# Spannungswandlung.net
KiCad netlist of a schematic drawn in Altium Designer
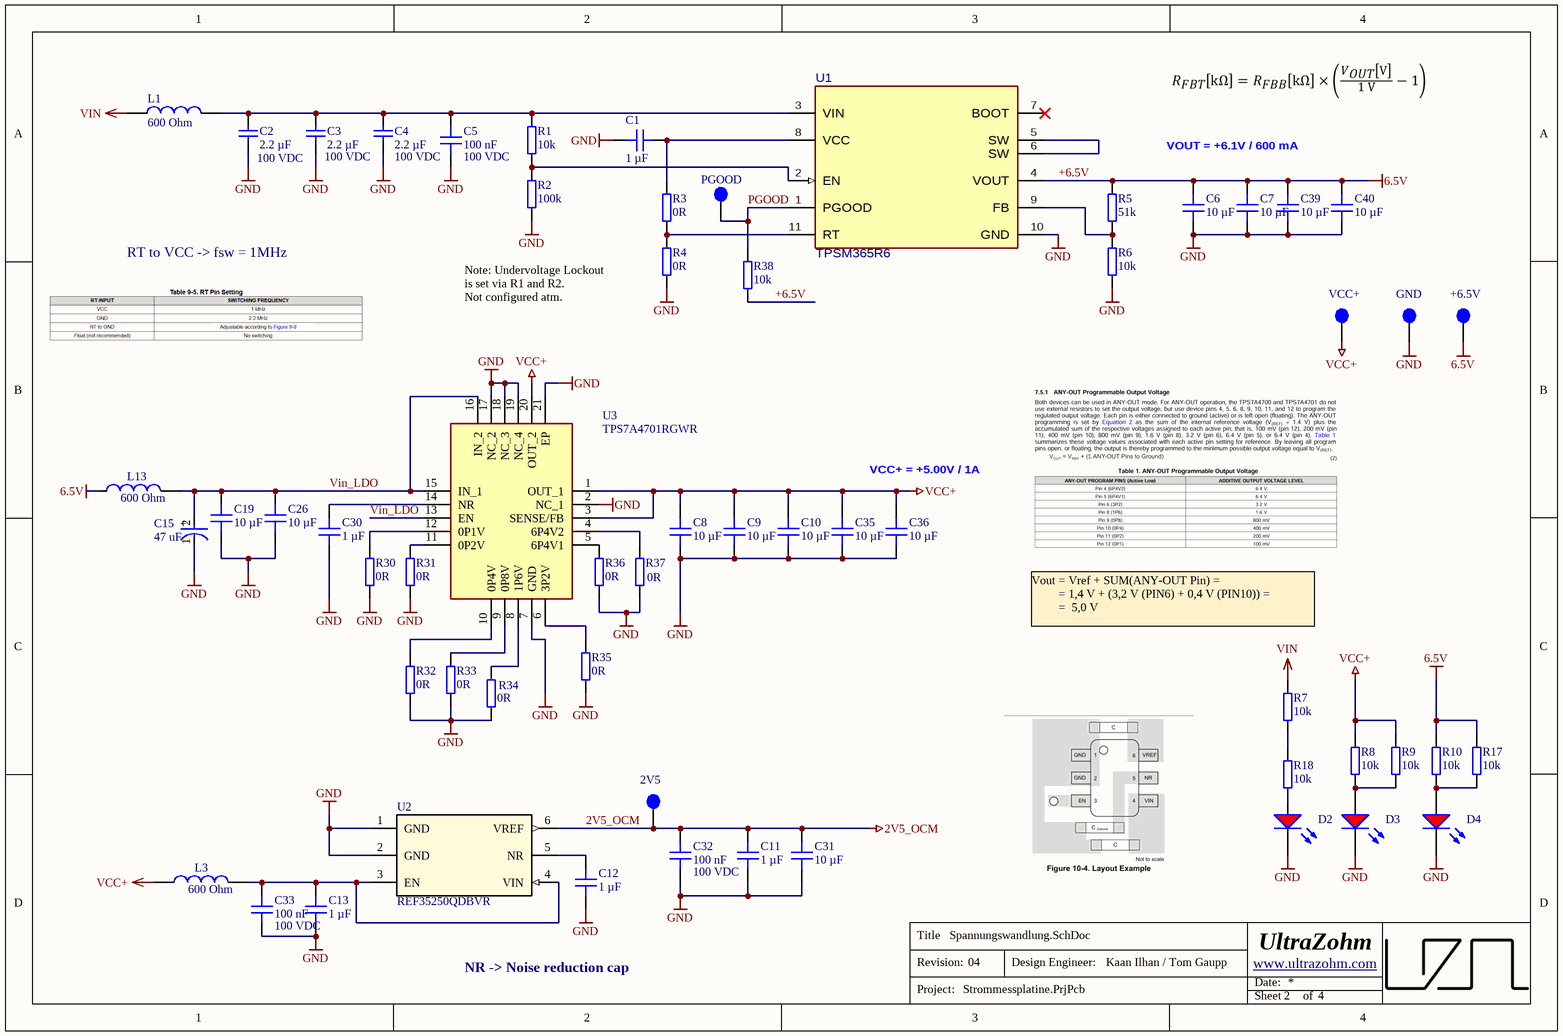
[diagram p0: Spannungswandlung.SchDoc]

(export (version "E")
  (design (tool "Eeschema 10.0.6"))
  (components
    (comp (ref "+6.5V")
      (value "6.5 V")
      (footprint "TP_1mm")
      (description "Testpoint 1mm")
      (fields
        (field (name "MANUFACTURER PART NUMBER") "NULL")
        (field (name "CREATED") "2018_06_25_AGeiger")
        (field (name "CREATED FROM") "AGeiger")
      )
      (libsource (lib "user") (part "TP_1mm"))
    )
    (comp (ref "2V5")
      (value "2V5")
      (footprint "TP_1mm")
      (description "Testpoint 1mm")
      (fields
        (field (name "MANUFACTURER PART NUMBER") "NULL")
        (field (name "CREATED") "2018_06_25_AGeiger")
        (field (name "CREATED FROM") "AGeiger")
      )
      (libsource (lib "user") (part "TP_1mm"))
    )
    (comp (ref "C1")
      (value "1 µF")
      (footprint "C_0603")
      (description "50V 1uF X5R ±10% 0603  Multilayer Ceramic Capacitors MLCC - SMD/SMT ROHS")
      (fields
        (field (name "MANUFACTURER PART NUMBER") "CL10A105KB8NNNC")
        (field (name "MANUFACTURER") "Samsung Electro-Mechanics")
        (field (name "CREATED FROM") "MGremer")
      )
      (libsource (lib "user") (part "Capacitor"))
    )
    (comp (ref "C2")
      (value "2.2 µF")
      (footprint "C_1210_TE")
      (description "100V 2.2uF X7R ±10% 1210 Multilayer Ceramic Capacitors MLCC - SMD/SMT ROHS")
      (fields
        (field (name "MANUFACTURER PART NUMBER") "FS32X225K101EGG")
        (field (name "MANUFACTURER") "PSA(Prosperity Dielectrics)")
        (field (name "VOLTAGE RATING") "100 VDC")
        (field (name "CREATED FROM") "AGeiger")
      )
      (libsource (lib "user") (part "CAP-NP"))
    )
    (comp (ref "C3")
      (value "2.2 µF")
      (footprint "C_1210_TE")
      (description "100V 2.2uF X7R ±10% 1210 Multilayer Ceramic Capacitors MLCC - SMD/SMT ROHS")
      (fields
        (field (name "MANUFACTURER PART NUMBER") "FS32X225K101EGG")
        (field (name "MANUFACTURER") "PSA(Prosperity Dielectrics)")
        (field (name "VOLTAGE RATING") "100 VDC")
        (field (name "CREATED FROM") "AGeiger")
      )
      (libsource (lib "user") (part "CAP-NP"))
    )
    (comp (ref "C4")
      (value "2.2 µF")
      (footprint "C_1210_TE")
      (description "100V 2.2uF X7R ±10% 1210 Multilayer Ceramic Capacitors MLCC - SMD/SMT ROHS")
      (fields
        (field (name "MANUFACTURER PART NUMBER") "FS32X225K101EGG")
        (field (name "MANUFACTURER") "PSA(Prosperity Dielectrics)")
        (field (name "VOLTAGE RATING") "100 VDC")
        (field (name "CREATED FROM") "AGeiger")
      )
      (libsource (lib "user") (part "CAP-NP"))
    )
    (comp (ref "C5")
      (value "100 nF")
      (footprint "C_0603")
      (description "100V 100nF X7S ±10% 0603 Multilayer Ceramic Capacitors MLCC - SMD/SMT ROHS")
      (fields
        (field (name "MANUFACTURER PART NUMBER") "C1608X7S2A104KT000N")
        (field (name "MANUFACTURER") "TDK")
        (field (name "VOLTAGE RATING") "100 VDC")
        (field (name "CREATED FROM") "AGeiger")
      )
      (libsource (lib "user") (part "Capacitor"))
    )
    (comp (ref "C6")
      (value "10 µF")
      (footprint "C0805")
      (description "Capacitor 0805, 35 VDC, 10 µF, X5R")
      (fields
        (field (name "MANUFACTURER PART NUMBER") "GRM21BR6YA106KE43L")
        (field (name "MANUFACTURER") "muRata")
        (field (name "CREATED FROM") "MGremer")
      )
      (libsource (lib "user") (part "Capacitor"))
    )
    (comp (ref "C7")
      (value "10 µF")
      (footprint "C0805")
      (description "Capacitor 0805, 35 VDC, 10 µF, X5R")
      (fields
        (field (name "MANUFACTURER PART NUMBER") "GRM21BR6YA106KE43L")
        (field (name "MANUFACTURER") "muRata")
        (field (name "CREATED FROM") "MGremer")
      )
      (libsource (lib "user") (part "Capacitor"))
    )
    (comp (ref "C8")
      (value "10 µF")
      (footprint "C0805")
      (description "Capacitor 0805, 35 VDC, 10 µF, X5R")
      (fields
        (field (name "MANUFACTURER PART NUMBER") "GRM21BR6YA106KE43L")
        (field (name "MANUFACTURER") "muRata")
        (field (name "CREATED FROM") "MGremer")
      )
      (libsource (lib "user") (part "Capacitor"))
    )
    (comp (ref "C9")
      (value "10 µF")
      (footprint "C0805")
      (description "Capacitor 0805, 35 VDC, 10 µF, X5R")
      (fields
        (field (name "MANUFACTURER PART NUMBER") "GRM21BR6YA106KE43L")
        (field (name "MANUFACTURER") "muRata")
        (field (name "CREATED FROM") "MGremer")
      )
      (libsource (lib "user") (part "Capacitor"))
    )
    (comp (ref "C10")
      (value "10 µF")
      (footprint "C0805")
      (description "Capacitor 0805, 35 VDC, 10 µF, X5R")
      (fields
        (field (name "MANUFACTURER PART NUMBER") "GRM21BR6YA106KE43L")
        (field (name "MANUFACTURER") "muRata")
        (field (name "CREATED FROM") "MGremer")
      )
      (libsource (lib "user") (part "Capacitor"))
    )
    (comp (ref "C11")
      (value "1 µF")
      (footprint "C_0603")
      (description "50V 1uF X5R ±10% 0603  Multilayer Ceramic Capacitors MLCC - SMD/SMT ROHS")
      (fields
        (field (name "MANUFACTURER PART NUMBER") "CL10A105KB8NNNC")
        (field (name "MANUFACTURER") "Samsung Electro-Mechanics")
        (field (name "CREATED FROM") "MGremer")
      )
      (libsource (lib "user") (part "Capacitor"))
    )
    (comp (ref "C12")
      (value "1 µF")
      (footprint "C_0603")
      (description "50V 1uF X5R ±10% 0603  Multilayer Ceramic Capacitors MLCC - SMD/SMT ROHS")
      (fields
        (field (name "MANUFACTURER PART NUMBER") "CL10A105KB8NNNC")
        (field (name "MANUFACTURER") "Samsung Electro-Mechanics")
        (field (name "CREATED FROM") "MGremer")
      )
      (libsource (lib "user") (part "Capacitor"))
    )
    (comp (ref "C13")
      (value "1 µF")
      (footprint "C_0603")
      (description "50V 1uF X5R ±10% 0603  Multilayer Ceramic Capacitors MLCC - SMD/SMT ROHS")
      (fields
        (field (name "MANUFACTURER PART NUMBER") "CL10A105KB8NNNC")
        (field (name "MANUFACTURER") "Samsung Electro-Mechanics")
        (field (name "CREATED FROM") "MGremer")
      )
      (libsource (lib "user") (part "Capacitor"))
    )
    (comp (ref "C15")
      (value "47 uF")
      (footprint "10TPE47MAZB")
      (description "Tantalum Capacitors - Polymer 10volts 47uF ESR 35mohm")
      (fields
        (field (name "MANUFACTURER PART NUMBER") "10TPE47MAZB")
        (field (name "MANUFACTURER") "Panasonic")
        (field (name "CREATED FROM") "Kilhan")
      )
      (libsource (lib "user") (part "10TPE47MAZB"))
    )
    (comp (ref "C19")
      (value "10 µF")
      (footprint "C0805")
      (description "Capacitor 0805, 35 VDC, 10 µF, X5R")
      (fields
        (field (name "MANUFACTURER PART NUMBER") "GRM21BR6YA106KE43L")
        (field (name "MANUFACTURER") "muRata")
        (field (name "CREATED FROM") "MGremer")
      )
      (libsource (lib "user") (part "Capacitor"))
    )
    (comp (ref "C26")
      (value "10 µF")
      (footprint "C0805")
      (description "Capacitor 0805, 35 VDC, 10 µF, X5R")
      (fields
        (field (name "MANUFACTURER PART NUMBER") "GRM21BR6YA106KE43L")
        (field (name "MANUFACTURER") "muRata")
        (field (name "CREATED FROM") "MGremer")
      )
      (libsource (lib "user") (part "Capacitor"))
    )
    (comp (ref "C30")
      (value "1 µF")
      (footprint "C_0603")
      (description "50V 1uF X5R ±10% 0603  Multilayer Ceramic Capacitors MLCC - SMD/SMT ROHS")
      (fields
        (field (name "MANUFACTURER PART NUMBER") "CL10A105KB8NNNC")
        (field (name "MANUFACTURER") "Samsung Electro-Mechanics")
        (field (name "CREATED FROM") "MGremer")
      )
      (libsource (lib "user") (part "Capacitor"))
    )
    (comp (ref "C31")
      (value "10 µF")
      (footprint "C0805")
      (description "Capacitor 0805, 35 VDC, 10 µF, X5R")
      (fields
        (field (name "MANUFACTURER PART NUMBER") "GRM21BR6YA106KE43L")
        (field (name "MANUFACTURER") "muRata")
        (field (name "CREATED FROM") "MGremer")
      )
      (libsource (lib "user") (part "Capacitor"))
    )
    (comp (ref "C32")
      (value "100 nF")
      (footprint "C_0603")
      (description "100V 100nF X7S ±10% 0603 Multilayer Ceramic Capacitors MLCC - SMD/SMT ROHS")
      (fields
        (field (name "MANUFACTURER PART NUMBER") "C1608X7S2A104KT000N")
        (field (name "MANUFACTURER") "TDK")
        (field (name "VOLTAGE RATING") "100 VDC")
        (field (name "CREATED FROM") "AGeiger")
      )
      (libsource (lib "user") (part "Capacitor"))
    )
    (comp (ref "C33")
      (value "100 nF")
      (footprint "C_0603")
      (description "100V 100nF X7S ±10% 0603 Multilayer Ceramic Capacitors MLCC - SMD/SMT ROHS")
      (fields
        (field (name "MANUFACTURER PART NUMBER") "C1608X7S2A104KT000N")
        (field (name "MANUFACTURER") "TDK")
        (field (name "VOLTAGE RATING") "100 VDC")
        (field (name "CREATED FROM") "AGeiger")
      )
      (libsource (lib "user") (part "Capacitor"))
    )
    (comp (ref "C35")
      (value "10 µF")
      (footprint "C0805")
      (description "Capacitor 0805, 35 VDC, 10 µF, X5R")
      (fields
        (field (name "MANUFACTURER PART NUMBER") "GRM21BR6YA106KE43L")
        (field (name "MANUFACTURER") "muRata")
        (field (name "CREATED FROM") "MGremer")
      )
      (libsource (lib "user") (part "Capacitor"))
    )
    (comp (ref "C36")
      (value "10 µF")
      (footprint "C0805")
      (description "Capacitor 0805, 35 VDC, 10 µF, X5R")
      (fields
        (field (name "MANUFACTURER PART NUMBER") "GRM21BR6YA106KE43L")
        (field (name "MANUFACTURER") "muRata")
        (field (name "CREATED FROM") "MGremer")
      )
      (libsource (lib "user") (part "Capacitor"))
    )
    (comp (ref "C39")
      (value "10 µF")
      (footprint "C0805")
      (description "Capacitor 0805, 35 VDC, 10 µF, X5R")
      (fields
        (field (name "MANUFACTURER PART NUMBER") "GRM21BR6YA106KE43L")
        (field (name "MANUFACTURER") "muRata")
        (field (name "CREATED FROM") "MGremer")
      )
      (libsource (lib "user") (part "Capacitor"))
    )
    (comp (ref "C40")
      (value "10 µF")
      (footprint "C0805")
      (description "Capacitor 0805, 35 VDC, 10 µF, X5R")
      (fields
        (field (name "MANUFACTURER PART NUMBER") "GRM21BR6YA106KE43L")
        (field (name "MANUFACTURER") "muRata")
        (field (name "CREATED FROM") "MGremer")
      )
      (libsource (lib "user") (part "Capacitor"))
    )
    (comp (ref "D2")
      (value "KT-0603R")
      (footprint "WL-SMCW_0603")
      (description "LED RED 520~625NM 90~100MCD@20MA TOP VIEW 0603 ROHS")
      (fields
        (field (name "MANUFACTURER") "Hubei KENTO Elec")
        (field (name "LCSC PART NUMBER") "C2286")
        (field (name "CREATED FROM") "T. Wendt")
      )
      (libsource (lib "user") (part "LED_Red"))
    )
    (comp (ref "D3")
      (value "KT-0603R")
      (footprint "WL-SMCW_0603")
      (description "LED RED 520~625NM 90~100MCD@20MA TOP VIEW 0603 ROHS")
      (fields
        (field (name "MANUFACTURER") "Hubei KENTO Elec")
        (field (name "LCSC PART NUMBER") "C2286")
        (field (name "CREATED FROM") "T. Wendt")
      )
      (libsource (lib "user") (part "LED_Red"))
    )
    (comp (ref "D4")
      (value "KT-0603R")
      (footprint "WL-SMCW_0603")
      (description "LED RED 520~625NM 90~100MCD@20MA TOP VIEW 0603 ROHS")
      (fields
        (field (name "MANUFACTURER") "Hubei KENTO Elec")
        (field (name "LCSC PART NUMBER") "C2286")
        (field (name "CREATED FROM") "T. Wendt")
      )
      (libsource (lib "user") (part "LED_Red"))
    )
    (comp (ref "GND")
      (value "Testpoint 1mm")
      (footprint "TP_1mm")
      (fields
        (field (name "MANUFACTURER PART NUMBER") "NULL")
        (field (name "CREATED") "2018_06_25_AGeiger")
        (field (name "CREATED FROM") "AGeiger")
      )
      (libsource (lib "user") (part "TP_1mm"))
    )
    (comp (ref "L1")
      (value "600 Ohm")
      (footprint "WE-CBF_0805_High Current")
      (description "Inductance, 0805, 100 MHz, 600 Ohm, 2 A")
      (fields
        (field (name "LCSC PART NUMBER") "C2661857")
        (field (name "MANUFACTURER PART NUMBER") "742792040")
        (field (name "CREATED FROM") "AGeiger")
      )
      (libsource (lib "user") (part "WE-CBF"))
    )
    (comp (ref "L3")
      (value "600 Ohm")
      (footprint "WE-CBF_0805_High Current")
      (description "Inductance, 0805, 100 MHz, 600 Ohm, 2 A")
      (fields
        (field (name "LCSC PART NUMBER") "C2661857")
        (field (name "MANUFACTURER PART NUMBER") "742792040")
        (field (name "CREATED FROM") "AGeiger")
      )
      (libsource (lib "user") (part "WE-CBF"))
    )
    (comp (ref "L13")
      (value "600 Ohm")
      (footprint "WE-CBF_0805_High Current")
      (description "Inductance, 0805, 100 MHz, 600 Ohm, 2 A")
      (fields
        (field (name "LCSC PART NUMBER") "C2661857")
        (field (name "MANUFACTURER PART NUMBER") "742792040")
        (field (name "CREATED FROM") "AGeiger")
      )
      (libsource (lib "user") (part "WE-CBF"))
    )
    (comp (ref "PGOOD")
      (value "Testpoint 1mm")
      (footprint "TP_1mm")
      (fields
        (field (name "MANUFACTURER PART NUMBER") "NULL")
        (field (name "CREATED") "2018_06_25_AGeiger")
        (field (name "CREATED FROM") "AGeiger")
      )
      (libsource (lib "user") (part "TP_1mm"))
    )
    (comp (ref "R1")
      (value "10k")
      (footprint "RES 0603_1608")
      (description "SMD resistor 1%")
      (fields
        (field (name "MANUFACTURER PART NUMBER") "0603WAF1002T5E")
        (field (name "MANUFACTURER") "UNI-ROYAL")
        (field (name "CREATED FROM") "AGeiger")
      )
      (libsource (lib "user") (part "Resistor"))
    )
    (comp (ref "R2")
      (value "100k")
      (footprint "RES 0603_1608")
      (description "SMD resistor 1%")
      (fields
        (field (name "MANUFACTURER PART NUMBER") "CRCW0603100KFKEAC")
        (field (name "MANUFACTURER") "Vishay")
        (field (name "CREATED FROM") "MGremer")
      )
      (libsource (lib "user") (part "Resistor"))
    )
    (comp (ref "R3")
      (value "0R")
      (footprint "RES 0603_1608")
      (description "SMD resistor E24 series")
      (fields
        (field (name "MANUFACTURER PART NUMBER") "RC0603JR-070RL")
        (field (name "MANUFACTURER") "YAGEO")
        (field (name "CREATED FROM") "MGremer")
      )
      (libsource (lib "user") (part "Resistor"))
    )
    (comp (ref "R4")
      (value "0R")
      (footprint "RES 0603_1608")
      (description "SMD resistor E24 series")
      (fields
        (field (name "MANUFACTURER PART NUMBER") "RC0603JR-070RL")
        (field (name "MANUFACTURER") "YAGEO")
        (field (name "CREATED FROM") "MGremer")
      )
      (libsource (lib "user") (part "Resistor"))
    )
    (comp (ref "R5")
      (value "51k")
      (footprint "R_0603_TE")
      (description "100mW Thick Film Resistors 75V ±100ppm/℃ ±1% 51kΩ 0603 Chip Resistor - Surface Mount ROHS")
      (fields
        (field (name "MANUFACTURER PART NUMBER") "0603WAF5102T5E")
        (field (name "MANUFACTURER") "UNI-ROYAL(Uniroyal Elec)")
        (field (name "CREATED FROM") "KIlhan")
      )
      (libsource (lib "user") (part "Resistor"))
    )
    (comp (ref "R6")
      (value "10k")
      (footprint "RES 0603_1608")
      (description "SMD resistor 1%")
      (fields
        (field (name "MANUFACTURER PART NUMBER") "0603WAF1002T5E")
        (field (name "MANUFACTURER") "UNI-ROYAL")
        (field (name "CREATED FROM") "AGeiger")
      )
      (libsource (lib "user") (part "Resistor"))
    )
    (comp (ref "R7")
      (value "10k")
      (footprint "RES 0603_1608")
      (description "SMD resistor 1%")
      (fields
        (field (name "MANUFACTURER PART NUMBER") "0603WAF1002T5E")
        (field (name "MANUFACTURER") "UNI-ROYAL")
        (field (name "CREATED FROM") "AGeiger")
      )
      (libsource (lib "user") (part "Resistor"))
    )
    (comp (ref "R8")
      (value "10k")
      (footprint "RES 0603_1608")
      (description "SMD resistor 1%")
      (fields
        (field (name "MANUFACTURER PART NUMBER") "0603WAF1002T5E")
        (field (name "MANUFACTURER") "UNI-ROYAL")
        (field (name "CREATED FROM") "AGeiger")
      )
      (libsource (lib "user") (part "Resistor"))
    )
    (comp (ref "R9")
      (value "10k")
      (footprint "RES 0603_1608")
      (description "SMD resistor 1%")
      (fields
        (field (name "MANUFACTURER PART NUMBER") "0603WAF1002T5E")
        (field (name "MANUFACTURER") "UNI-ROYAL")
        (field (name "CREATED FROM") "AGeiger")
      )
      (libsource (lib "user") (part "Resistor"))
    )
    (comp (ref "R10")
      (value "10k")
      (footprint "RES 0603_1608")
      (description "SMD resistor 1%")
      (fields
        (field (name "MANUFACTURER PART NUMBER") "0603WAF1002T5E")
        (field (name "MANUFACTURER") "UNI-ROYAL")
        (field (name "CREATED FROM") "AGeiger")
      )
      (libsource (lib "user") (part "Resistor"))
    )
    (comp (ref "R17")
      (value "10k")
      (footprint "RES 0603_1608")
      (description "SMD resistor 1%")
      (fields
        (field (name "MANUFACTURER PART NUMBER") "0603WAF1002T5E")
        (field (name "MANUFACTURER") "UNI-ROYAL")
        (field (name "CREATED FROM") "AGeiger")
      )
      (libsource (lib "user") (part "Resistor"))
    )
    (comp (ref "R18")
      (value "10k")
      (footprint "RES 0603_1608")
      (description "SMD resistor 1%")
      (fields
        (field (name "MANUFACTURER PART NUMBER") "0603WAF1002T5E")
        (field (name "MANUFACTURER") "UNI-ROYAL")
        (field (name "CREATED FROM") "AGeiger")
      )
      (libsource (lib "user") (part "Resistor"))
    )
    (comp (ref "R30")
      (value "0R")
      (footprint "RES 0603_1608")
      (description "SMD resistor E24 series")
      (fields
        (field (name "MANUFACTURER PART NUMBER") "RC0603JR-070RL")
        (field (name "MANUFACTURER") "YAGEO")
        (field (name "CREATED FROM") "MGremer")
      )
      (libsource (lib "user") (part "Resistor"))
    )
    (comp (ref "R31")
      (value "0R")
      (footprint "RES 0603_1608")
      (description "SMD resistor E24 series")
      (fields
        (field (name "MANUFACTURER PART NUMBER") "RC0603JR-070RL")
        (field (name "MANUFACTURER") "YAGEO")
        (field (name "CREATED FROM") "MGremer")
      )
      (libsource (lib "user") (part "Resistor"))
    )
    (comp (ref "R32")
      (value "0R")
      (footprint "RES 0603_1608")
      (description "SMD resistor E24 series")
      (fields
        (field (name "MANUFACTURER PART NUMBER") "RC0603JR-070RL")
        (field (name "MANUFACTURER") "YAGEO")
        (field (name "CREATED FROM") "MGremer")
      )
      (libsource (lib "user") (part "Resistor"))
    )
    (comp (ref "R33")
      (value "0R")
      (footprint "RES 0603_1608")
      (description "SMD resistor E24 series")
      (fields
        (field (name "MANUFACTURER PART NUMBER") "RC0603JR-070RL")
        (field (name "MANUFACTURER") "YAGEO")
        (field (name "CREATED FROM") "MGremer")
      )
      (libsource (lib "user") (part "Resistor"))
    )
    (comp (ref "R34")
      (value "0R")
      (footprint "RES 0603_1608")
      (description "SMD resistor E24 series")
      (fields
        (field (name "MANUFACTURER PART NUMBER") "RC0603JR-070RL")
        (field (name "MANUFACTURER") "YAGEO")
        (field (name "CREATED FROM") "MGremer")
      )
      (libsource (lib "user") (part "Resistor"))
    )
    (comp (ref "R35")
      (value "0R")
      (footprint "RES 0603_1608")
      (description "SMD resistor E24 series")
      (fields
        (field (name "MANUFACTURER PART NUMBER") "RC0603JR-070RL")
        (field (name "MANUFACTURER") "YAGEO")
        (field (name "CREATED FROM") "MGremer")
      )
      (libsource (lib "user") (part "Resistor"))
    )
    (comp (ref "R36")
      (value "0R")
      (footprint "RES 0603_1608")
      (description "SMD resistor E24 series")
      (fields
        (field (name "MANUFACTURER PART NUMBER") "RC0603JR-070RL")
        (field (name "MANUFACTURER") "YAGEO")
        (field (name "CREATED FROM") "MGremer")
      )
      (libsource (lib "user") (part "Resistor"))
    )
    (comp (ref "R37")
      (value "0R")
      (footprint "RES 0603_1608")
      (description "SMD resistor E24 series")
      (fields
        (field (name "MANUFACTURER PART NUMBER") "RC0603JR-070RL")
        (field (name "MANUFACTURER") "YAGEO")
        (field (name "CREATED FROM") "MGremer")
      )
      (libsource (lib "user") (part "Resistor"))
    )
    (comp (ref "R38")
      (value "10k")
      (footprint "RES 0603_1608")
      (description "SMD resistor 1%")
      (fields
        (field (name "MANUFACTURER PART NUMBER") "0603WAF1002T5E")
        (field (name "MANUFACTURER") "UNI-ROYAL")
        (field (name "CREATED FROM") "AGeiger")
      )
      (libsource (lib "user") (part "Resistor"))
    )
    (comp (ref "U1")
      (value "TPSM365R6")
      (footprint "RDN0011A-MFG")
      (description "3-V to 65-V input, 1-V to 13-V output, 0.6-A synchronous buck converter power module")
      (fields
        (field (name "MANUFACTURER PART NUMBER") "TPSM365R6FRDNR")
        (field (name "MANUFACTURER") "Texas Instruments")
        (field (name "CREATED FROM") "KIlhan")
      )
      (libsource (lib "user") (part "TPSM365"))
    )
    (comp (ref "U2")
      (value "REF35250QDBVR")
      (footprint "TI_SOT23_6-Leads")
      (description "2.5V ±0.05% 2.75V~6V 10mA Fixed SOT-23-6 Voltage Reference ROHS")
      (fields
        (field (name "MANUFACTURER") "Texas Instruments")
        (field (name "LCSC PART NUMBER") "C6265005")
        (field (name "CREATED FROM") "KIlhan")
      )
      (libsource (lib "user") (part "REF35250QDBVR"))
    )
    (comp (ref "U3")
      (value "TPS7A4701RGWR")
      (footprint "QFN65P500X500X100-21N-D")
      (description "1-A, 36-V, low-noise, high-PSRR, low-dropout voltage regulator with enable")
      (fields
        (field (name "MOUSER PART NUMBER") "595-TPS7A4701RGWR")
        (field (name "MANUFACTURER PART NUMBER") "TPS7A4700RGWR")
        (field (name "CREATED FROM") "KIlhan")
      )
      (libsource (lib "user") (part "TPS7A4701RGWR"))
    )
    (comp (ref "VCC+")
      (value "VCC+")
      (footprint "TP_1mm")
      (description "Testpoint 1mm")
      (fields
        (field (name "MANUFACTURER PART NUMBER") "NULL")
        (field (name "CREATED") "2018_06_25_AGeiger")
        (field (name "CREATED FROM") "AGeiger")
      )
      (libsource (lib "user") (part "TP_1mm"))
    )
  )
  (nets
    (net (code "2") (name "/PGOOD") (class "Default")
      (node (ref "PGOOD") (pin "1") (pintype "passive"))
      (node (ref "R38") (pin "1") (pinfunction "1_1") (pintype "passive"))
      (node (ref "U1") (pin "1") (pinfunction "PGOOD_1") (pintype "open_collector"))
    )
    (net (code "3") (name "/Vin_LDO") (class "Default")
      (node (ref "C15") (pin "2") (pinfunction "A_2") (pintype "passive"))
      (node (ref "C19") (pin "2") (pinfunction "2_2") (pintype "passive"))
      (node (ref "C26") (pin "2") (pinfunction "2_2") (pintype "passive"))
      (node (ref "L13") (pin "2") (pinfunction "2_2") (pintype "passive"))
      (node (ref "U3") (pin "13") (pinfunction "EN_13") (pintype "passive"))
      (node (ref "U3") (pin "15") (pinfunction "IN_1_15") (pintype "passive"))
      (node (ref "U3") (pin "16") (pinfunction "IN_2_16") (pintype "passive"))
    )
    (net (code "4") (name "2V5_OCM") (class "Default")
      (node (ref "2V5") (pin "1") (pintype "passive"))
      (node (ref "C11") (pin "2") (pinfunction "2_2") (pintype "passive"))
      (node (ref "C31") (pin "2") (pinfunction "2_2") (pintype "passive"))
      (node (ref "C32") (pin "2") (pinfunction "2_2") (pintype "passive"))
      (node (ref "U2") (pin "6") (pinfunction "VREF_6") (pintype "output"))
    )
    (net (code "5") (name "6.5V") (class "Default")
      (node (ref "+6.5V") (pin "1") (pintype "passive"))
      (node (ref "C39") (pin "2") (pinfunction "2_2") (pintype "passive"))
      (node (ref "C40") (pin "2") (pinfunction "2_2") (pintype "passive"))
      (node (ref "C6") (pin "2") (pinfunction "2_2") (pintype "passive"))
      (node (ref "C7") (pin "2") (pinfunction "2_2") (pintype "passive"))
      (node (ref "L13") (pin "1") (pinfunction "1_1") (pintype "passive"))
      (node (ref "R10") (pin "1") (pinfunction "1_1") (pintype "passive"))
      (node (ref "R17") (pin "1") (pinfunction "1_1") (pintype "passive"))
      (node (ref "R38") (pin "2") (pinfunction "2_2") (pintype "passive"))
      (node (ref "R5") (pin "2") (pinfunction "2_2") (pintype "passive"))
      (node (ref "U1") (pin "4") (pinfunction "VOUT_4") (pintype "power_in"))
    )
    (net (code "6") (name "GND") (class "Default")
      (node (ref "C1") (pin "2") (pinfunction "2_2") (pintype "passive"))
      (node (ref "C10") (pin "1") (pinfunction "1_1") (pintype "passive"))
      (node (ref "C11") (pin "1") (pinfunction "1_1") (pintype "passive"))
      (node (ref "C12") (pin "1") (pinfunction "1_1") (pintype "passive"))
      (node (ref "C13") (pin "1") (pinfunction "1_1") (pintype "passive"))
      (node (ref "C15") (pin "1") (pinfunction "C_1") (pintype "passive"))
      (node (ref "C19") (pin "1") (pinfunction "1_1") (pintype "passive"))
      (node (ref "C2") (pin "2") (pinfunction "2_2") (pintype "passive"))
      (node (ref "C26") (pin "1") (pinfunction "1_1") (pintype "passive"))
      (node (ref "C3") (pin "2") (pinfunction "2_2") (pintype "passive"))
      (node (ref "C30") (pin "2") (pinfunction "2_2") (pintype "passive"))
      (node (ref "C31") (pin "1") (pinfunction "1_1") (pintype "passive"))
      (node (ref "C32") (pin "1") (pinfunction "1_1") (pintype "passive"))
      (node (ref "C33") (pin "1") (pinfunction "1_1") (pintype "passive"))
      (node (ref "C35") (pin "1") (pinfunction "1_1") (pintype "passive"))
      (node (ref "C36") (pin "1") (pinfunction "1_1") (pintype "passive"))
      (node (ref "C39") (pin "1") (pinfunction "1_1") (pintype "passive"))
      (node (ref "C4") (pin "2") (pinfunction "2_2") (pintype "passive"))
      (node (ref "C40") (pin "1") (pinfunction "1_1") (pintype "passive"))
      (node (ref "C5") (pin "1") (pinfunction "1_1") (pintype "passive"))
      (node (ref "C6") (pin "1") (pinfunction "1_1") (pintype "passive"))
      (node (ref "C7") (pin "1") (pinfunction "1_1") (pintype "passive"))
      (node (ref "C8") (pin "1") (pinfunction "1_1") (pintype "passive"))
      (node (ref "C9") (pin "1") (pinfunction "1_1") (pintype "passive"))
      (node (ref "D2") (pin "1") (pinfunction "K_1") (pintype "passive"))
      (node (ref "D3") (pin "1") (pinfunction "K_1") (pintype "passive"))
      (node (ref "D4") (pin "1") (pinfunction "K_1") (pintype "passive"))
      (node (ref "GND") (pin "1") (pintype "passive"))
      (node (ref "R2") (pin "2") (pinfunction "2_2") (pintype "passive"))
      (node (ref "R30") (pin "2") (pinfunction "2_2") (pintype "passive"))
      (node (ref "R31") (pin "1") (pinfunction "1_1") (pintype "passive"))
      (node (ref "R32") (pin "1") (pinfunction "1_1") (pintype "passive"))
      (node (ref "R33") (pin "1") (pinfunction "1_1") (pintype "passive"))
      (node (ref "R34") (pin "1") (pinfunction "1_1") (pintype "passive"))
      (node (ref "R35") (pin "2") (pinfunction "2_2") (pintype "passive"))
      (node (ref "R36") (pin "1") (pinfunction "1_1") (pintype "passive"))
      (node (ref "R37") (pin "1") (pinfunction "1_1") (pintype "passive"))
      (node (ref "R4") (pin "1") (pinfunction "1_1") (pintype "passive"))
      (node (ref "R6") (pin "2") (pinfunction "2_2") (pintype "passive"))
      (node (ref "U1") (pin "10") (pinfunction "GND_10") (pintype "power_in"))
      (node (ref "U2") (pin "1") (pinfunction "GND_1") (pintype "power_in"))
      (node (ref "U2") (pin "2") (pinfunction "GND_2") (pintype "power_in"))
      (node (ref "U3") (pin "17") (pinfunction "NC_2_17") (pintype "passive"))
      (node (ref "U3") (pin "18") (pinfunction "NC_3_18") (pintype "passive"))
      (node (ref "U3") (pin "19") (pinfunction "NC_4_19") (pintype "passive"))
      (node (ref "U3") (pin "2") (pinfunction "NC_1_2") (pintype "passive"))
      (node (ref "U3") (pin "21") (pinfunction "EP_21") (pintype "passive"))
      (node (ref "U3") (pin "7") (pinfunction "GND_7") (pintype "passive"))
    )
    (net (code "7") (name "Net-(D2-A)") (class "Default")
      (node (ref "D2") (pin "2") (pinfunction "A_2") (pintype "passive"))
      (node (ref "R18") (pin "2") (pinfunction "2_2") (pintype "passive"))
    )
    (net (code "8") (name "Net-(D3-A)") (class "Default")
      (node (ref "D3") (pin "2") (pinfunction "A_2") (pintype "passive"))
      (node (ref "R8") (pin "2") (pinfunction "2_2") (pintype "passive"))
      (node (ref "R9") (pin "2") (pinfunction "2_2") (pintype "passive"))
    )
    (net (code "9") (name "Net-(D4-A)") (class "Default")
      (node (ref "D4") (pin "2") (pinfunction "A_2") (pintype "passive"))
      (node (ref "R10") (pin "2") (pinfunction "2_2") (pintype "passive"))
      (node (ref "R17") (pin "2") (pinfunction "2_2") (pintype "passive"))
    )
    (net (code "10") (name "Net-(R18-Pad1)") (class "Default")
      (node (ref "R18") (pin "1") (pinfunction "1_1") (pintype "passive"))
      (node (ref "R7") (pin "2") (pinfunction "2_2") (pintype "passive"))
    )
    (net (code "11") (name "Net-(U1-EN)") (class "Default")
      (node (ref "R1") (pin "1") (pinfunction "1_1") (pintype "passive"))
      (node (ref "R2") (pin "1") (pinfunction "1_1") (pintype "passive"))
      (node (ref "U1") (pin "2") (pinfunction "EN_2") (pintype "input"))
    )
    (net (code "12") (name "Net-(U1-FB)") (class "Default")
      (node (ref "R5") (pin "1") (pinfunction "1_1") (pintype "passive"))
      (node (ref "R6") (pin "1") (pinfunction "1_1") (pintype "passive"))
      (node (ref "U1") (pin "9") (pinfunction "FB_9") (pintype "passive"))
    )
    (net (code "13") (name "Net-(U1-RT)") (class "Default")
      (node (ref "R3") (pin "1") (pinfunction "1_1") (pintype "passive"))
      (node (ref "R4") (pin "2") (pinfunction "2_2") (pintype "passive"))
      (node (ref "U1") (pin "11") (pinfunction "RT_11") (pintype "passive"))
    )
    (net (code "14") (name "Net-(U1-SW-Pad5)") (class "Default")
      (node (ref "U1") (pin "5") (pinfunction "SW_5") (pintype "passive"))
      (node (ref "U1") (pin "6") (pinfunction "SW_6") (pintype "passive"))
    )
    (net (code "15") (name "Net-(U1-VCC)") (class "Default")
      (node (ref "C1") (pin "1") (pinfunction "1_1") (pintype "passive"))
      (node (ref "R3") (pin "2") (pinfunction "2_2") (pintype "passive"))
      (node (ref "U1") (pin "8") (pinfunction "VCC_8") (pintype "power_in"))
    )
    (net (code "16") (name "Net-(U1-VIN)") (class "Default")
      (node (ref "C2") (pin "1") (pinfunction "1_1") (pintype "passive"))
      (node (ref "C3") (pin "1") (pinfunction "1_1") (pintype "passive"))
      (node (ref "C4") (pin "1") (pinfunction "1_1") (pintype "passive"))
      (node (ref "C5") (pin "2") (pinfunction "2_2") (pintype "passive"))
      (node (ref "L1") (pin "2") (pinfunction "2_2") (pintype "passive"))
      (node (ref "R1") (pin "2") (pinfunction "2_2") (pintype "passive"))
      (node (ref "U1") (pin "3") (pinfunction "VIN_3") (pintype "power_in"))
    )
    (net (code "17") (name "Net-(U2-EN)") (class "Default")
      (node (ref "C13") (pin "2") (pinfunction "2_2") (pintype "passive"))
      (node (ref "C33") (pin "2") (pinfunction "2_2") (pintype "passive"))
      (node (ref "L3") (pin "2") (pinfunction "2_2") (pintype "passive"))
      (node (ref "U2") (pin "3") (pinfunction "EN_3") (pintype "passive"))
      (node (ref "U2") (pin "4") (pinfunction "VIN_4") (pintype "input"))
    )
    (net (code "18") (name "Net-(U2-NR)") (class "Default")
      (node (ref "C12") (pin "2") (pinfunction "2_2") (pintype "passive"))
      (node (ref "U2") (pin "5") (pinfunction "NR_5") (pintype "passive"))
    )
    (net (code "19") (name "Net-(U3-0P1V)") (class "Default")
      (node (ref "R30") (pin "1") (pinfunction "1_1") (pintype "passive"))
      (node (ref "U3") (pin "12") (pinfunction "0P1V_12") (pintype "passive"))
    )
    (net (code "20") (name "Net-(U3-0P2V)") (class "Default")
      (node (ref "R31") (pin "2") (pinfunction "2_2") (pintype "passive"))
      (node (ref "U3") (pin "11") (pinfunction "0P2V_11") (pintype "passive"))
    )
    (net (code "21") (name "Net-(U3-0P4V)") (class "Default")
      (node (ref "R32") (pin "2") (pinfunction "2_2") (pintype "passive"))
      (node (ref "U3") (pin "10") (pinfunction "0P4V_10") (pintype "passive"))
    )
    (net (code "22") (name "Net-(U3-0P8V)") (class "Default")
      (node (ref "R33") (pin "2") (pinfunction "2_2") (pintype "passive"))
      (node (ref "U3") (pin "9") (pinfunction "0P8V_9") (pintype "passive"))
    )
    (net (code "23") (name "Net-(U3-1P6V)") (class "Default")
      (node (ref "R34") (pin "2") (pinfunction "2_2") (pintype "passive"))
      (node (ref "U3") (pin "8") (pinfunction "1P6V_8") (pintype "passive"))
    )
    (net (code "24") (name "Net-(U3-3P2V)") (class "Default")
      (node (ref "R35") (pin "1") (pinfunction "1_1") (pintype "passive"))
      (node (ref "U3") (pin "6") (pinfunction "3P2V_6") (pintype "passive"))
    )
    (net (code "25") (name "Net-(U3-6P4V1)") (class "Default")
      (node (ref "R36") (pin "2") (pinfunction "2_2") (pintype "passive"))
      (node (ref "U3") (pin "5") (pinfunction "6P4V1_5") (pintype "passive"))
    )
    (net (code "26") (name "Net-(U3-6P4V2)") (class "Default")
      (node (ref "R37") (pin "2") (pinfunction "2_2") (pintype "passive"))
      (node (ref "U3") (pin "4") (pinfunction "6P4V2_4") (pintype "passive"))
    )
    (net (code "27") (name "Net-(U3-NR)") (class "Default")
      (node (ref "C30") (pin "1") (pinfunction "1_1") (pintype "passive"))
      (node (ref "U3") (pin "14") (pinfunction "NR_14") (pintype "passive"))
    )
    (net (code "28") (name "VCC+") (class "Default")
      (node (ref "C10") (pin "2") (pinfunction "2_2") (pintype "passive"))
      (node (ref "C35") (pin "2") (pinfunction "2_2") (pintype "passive"))
      (node (ref "C36") (pin "2") (pinfunction "2_2") (pintype "passive"))
      (node (ref "C8") (pin "2") (pinfunction "2_2") (pintype "passive"))
      (node (ref "C9") (pin "2") (pinfunction "2_2") (pintype "passive"))
      (node (ref "L3") (pin "1") (pinfunction "1_1") (pintype "passive"))
      (node (ref "R8") (pin "1") (pinfunction "1_1") (pintype "passive"))
      (node (ref "R9") (pin "1") (pinfunction "1_1") (pintype "passive"))
      (node (ref "U3") (pin "1") (pinfunction "OUT_1_1") (pintype "passive"))
      (node (ref "U3") (pin "20") (pinfunction "OUT_2_20") (pintype "passive"))
      (node (ref "U3") (pin "3") (pinfunction "SENSE/FB_3") (pintype "passive"))
      (node (ref "VCC+") (pin "1") (pintype "passive"))
    )
    (net (code "29") (name "VIN") (class "Default")
      (node (ref "L1") (pin "1") (pinfunction "1_1") (pintype "passive"))
      (node (ref "R7") (pin "1") (pinfunction "1_1") (pintype "passive"))
    )
    (net (code "30") (name "unconnected-(U1-BOOT-Pad7)") (class "Default")
      (node (ref "U1") (pin "7") (pinfunction "BOOT_7") (pintype "passive+no_connect"))
    )
  )
)
